# ETHERNET.net
KiCad netlist of a schematic drawn in Altium Designer
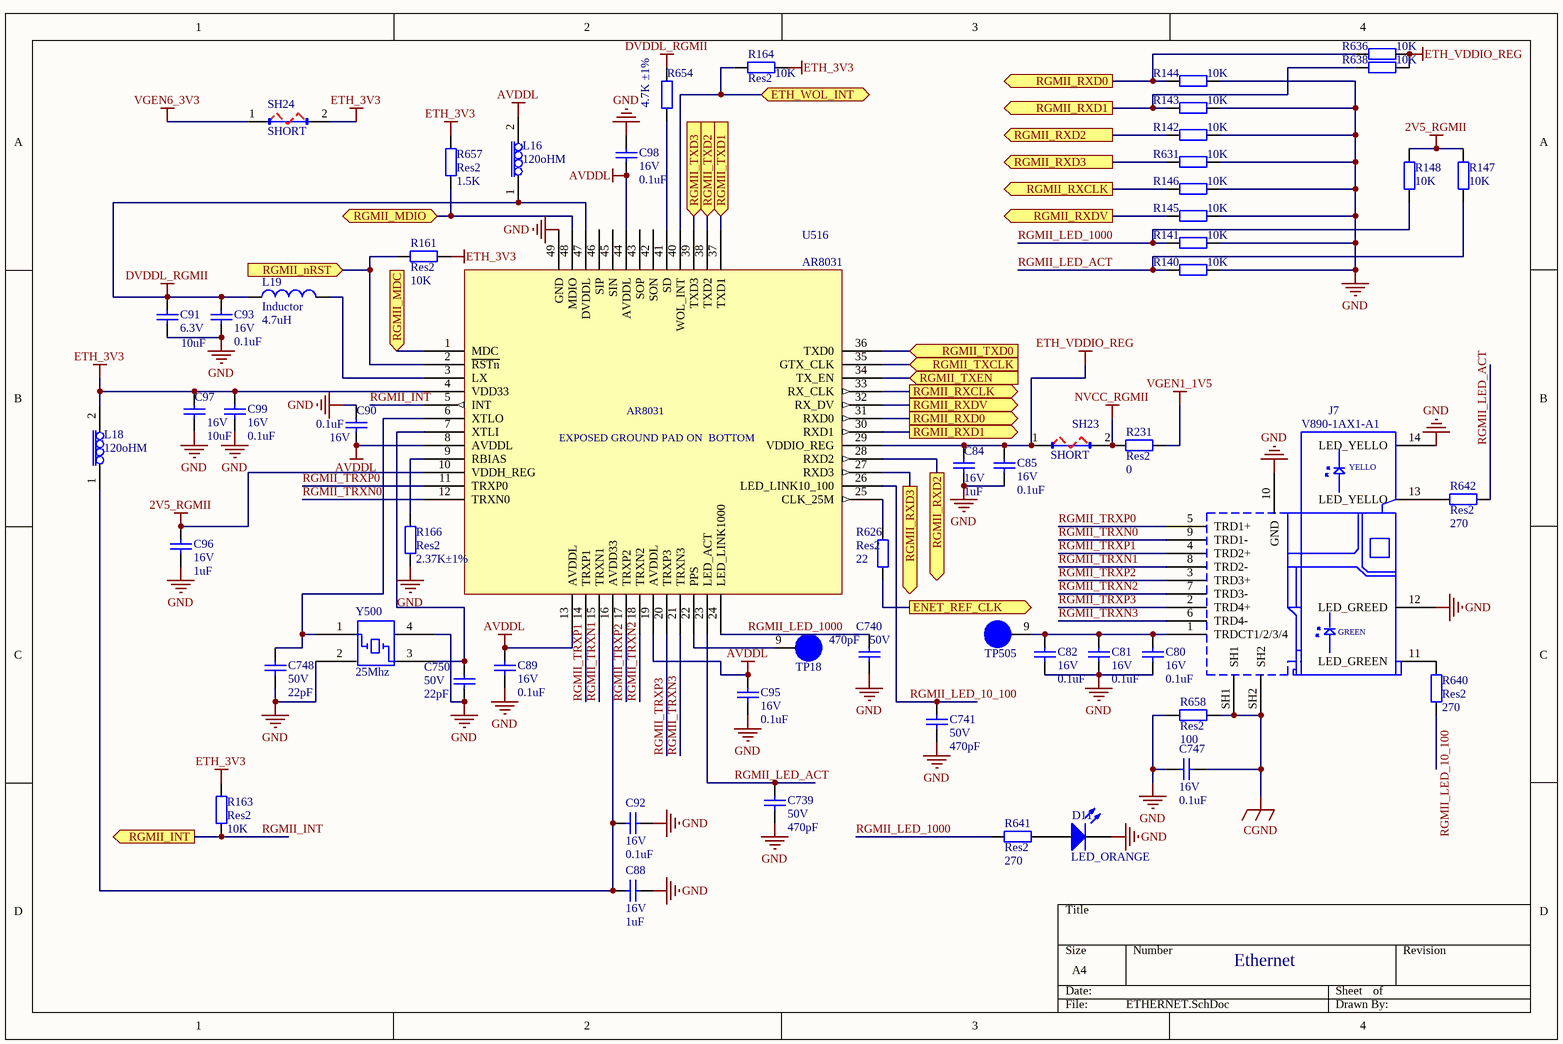
[diagram p0: ETHERNET.SchDoc]

(export (version "E")
  (design (tool "Eeschema 10.0.6"))
  (components
    (comp (ref "C80")
      (value "16V")
      (footprint "0402")
      (description "Capacitor")
      (fields (field (name "ALTIUM_VALUE") "0.1uF") (field (name "PUBLISHER") "Altium Limited"))
      (libsource (lib "Miscellaneous Devices") (part "Cap"))
    )
    (comp (ref "C81")
      (value "16V")
      (footprint "0402")
      (description "Capacitor")
      (fields (field (name "ALTIUM_VALUE") "0.1uF") (field (name "PUBLISHER") "Altium Limited"))
      (libsource (lib "Miscellaneous Devices") (part "Cap"))
    )
    (comp (ref "C82")
      (value "16V")
      (footprint "0402")
      (description "Capacitor")
      (fields (field (name "ALTIUM_VALUE") "0.1uF") (field (name "PUBLISHER") "Altium Limited"))
      (libsource (lib "Miscellaneous Devices") (part "Cap"))
    )
    (comp (ref "C84")
      (value "16V")
      (footprint "0603")
      (description "Capacitor")
      (fields (field (name "ALTIUM_VALUE") "1uF") (field (name "PUBLISHER") "Altium Limited"))
      (libsource (lib "Miscellaneous Devices") (part "Cap"))
    )
    (comp (ref "C85")
      (value "16V")
      (footprint "0402")
      (description "Capacitor")
      (fields (field (name "ALTIUM_VALUE") "0.1uF") (field (name "PUBLISHER") "Altium Limited"))
      (libsource (lib "Miscellaneous Devices") (part "Cap"))
    )
    (comp (ref "C88")
      (value "16V")
      (footprint "0603")
      (description "Capacitor")
      (fields (field (name "ALTIUM_VALUE") "1uF") (field (name "PUBLISHER") "Altium Limited"))
      (libsource (lib "Miscellaneous Devices") (part "Cap"))
    )
    (comp (ref "C89")
      (value "16V")
      (footprint "0402")
      (description "Capacitor")
      (fields (field (name "ALTIUM_VALUE") "0.1uF") (field (name "PUBLISHER") "Altium Limited"))
      (libsource (lib "Miscellaneous Devices") (part "Cap"))
    )
    (comp (ref "C90")
      (value "16V")
      (footprint "0402")
      (description "Capacitor")
      (fields (field (name "ALTIUM_VALUE") "0.1uF") (field (name "PUBLISHER") "Altium Limited"))
      (libsource (lib "Miscellaneous Devices") (part "Cap"))
    )
    (comp (ref "C91")
      (value "6.3V")
      (footprint "0603")
      (description "Capacitor")
      (fields (field (name "ALTIUM_VALUE") "10uF") (field (name "PUBLISHER") "Altium Limited"))
      (libsource (lib "Miscellaneous Devices") (part "Cap"))
    )
    (comp (ref "C92")
      (value "16V")
      (footprint "0402")
      (description "Capacitor")
      (fields (field (name "ALTIUM_VALUE") "0.1uF") (field (name "PUBLISHER") "Altium Limited"))
      (libsource (lib "Miscellaneous Devices") (part "Cap"))
    )
    (comp (ref "C93")
      (value "16V")
      (footprint "0402")
      (description "Capacitor")
      (fields (field (name "ALTIUM_VALUE") "0.1uF") (field (name "PUBLISHER") "Altium Limited"))
      (libsource (lib "Miscellaneous Devices") (part "Cap"))
    )
    (comp (ref "C95")
      (value "16V")
      (footprint "0402")
      (description "Capacitor")
      (fields (field (name "ALTIUM_VALUE") "0.1uF") (field (name "PUBLISHER") "Altium Limited"))
      (libsource (lib "Miscellaneous Devices") (part "Cap"))
    )
    (comp (ref "C96")
      (value "16V")
      (footprint "0603")
      (description "Capacitor")
      (fields (field (name "ALTIUM_VALUE") "1uF") (field (name "PUBLISHER") "Altium Limited"))
      (libsource (lib "Miscellaneous Devices") (part "Cap"))
    )
    (comp (ref "C97")
      (value "16V")
      (footprint "0603")
      (description "Capacitor")
      (fields (field (name "ALTIUM_VALUE") "10uF") (field (name "PUBLISHER") "Altium Limited"))
      (libsource (lib "Miscellaneous Devices") (part "Cap"))
    )
    (comp (ref "C98")
      (value "16V")
      (footprint "0402")
      (description "Capacitor")
      (fields (field (name "ALTIUM_VALUE") "0.1uF") (field (name "PUBLISHER") "Altium Limited"))
      (libsource (lib "Miscellaneous Devices") (part "Cap"))
    )
    (comp (ref "C99")
      (value "16V")
      (footprint "0402")
      (description "Capacitor")
      (fields (field (name "ALTIUM_VALUE") "0.1uF") (field (name "PUBLISHER") "Altium Limited"))
      (libsource (lib "Miscellaneous Devices") (part "Cap"))
    )
    (comp (ref "C739")
      (value "50V")
      (footprint "0402")
      (description "Capacitor")
      (fields (field (name "ALTIUM_VALUE") "470pF") (field (name "PUBLISHER") "Altium Limited"))
      (libsource (lib "Miscellaneous Devices") (part "Cap"))
    )
    (comp (ref "C740")
      (value "50V")
      (footprint "0402")
      (description "Capacitor")
      (fields (field (name "ALTIUM_VALUE") "470pF") (field (name "PUBLISHER") "Altium Limited"))
      (libsource (lib "Miscellaneous Devices") (part "Cap"))
    )
    (comp (ref "C741")
      (value "50V")
      (footprint "0402")
      (description "Capacitor")
      (fields (field (name "ALTIUM_VALUE") "470pF") (field (name "PUBLISHER") "Altium Limited"))
      (libsource (lib "Miscellaneous Devices") (part "Cap"))
    )
    (comp (ref "C747")
      (value "16V")
      (footprint "0402")
      (description "Capacitor")
      (fields (field (name "ALTIUM_VALUE") "0.1uF") (field (name "PUBLISHER") "Altium Limited"))
      (libsource (lib "Miscellaneous Devices") (part "Cap"))
    )
    (comp (ref "C748")
      (value "50V")
      (footprint "0402")
      (description "Capacitor")
      (fields (field (name "ALTIUM_VALUE") "22pF") (field (name "PUBLISHER") "Altium Limited"))
      (libsource (lib "Miscellaneous Devices") (part "Cap"))
    )
    (comp (ref "C750")
      (value "50V")
      (footprint "0402")
      (description "Capacitor")
      (fields (field (name "ALTIUM_VALUE") "22pF") (field (name "PUBLISHER") "Altium Limited"))
      (libsource (lib "Miscellaneous Devices") (part "Cap"))
    )
    (comp (ref "D11")
      (value "LED_ORANGE")
      (footprint "LED_0603")
      (description "Typical INFRARED GaAs LED")
      (fields (field (name "PUBLISHER") "Altium Limited"))
      (libsource (lib "Miscellaneous Devices") (part "LED0"))
    )
    (comp (ref "J7")
      (value "V890-1AX1-A1")
      (footprint "V890-1AX1-A1")
      (libsource (lib "IMX6DL") (part "Ethernet PORT"))
    )
    (comp (ref "L16") (value "120oHM") (footprint "0603") (libsource (lib "IMX6DL") (part "magnetic BEAD")))
    (comp (ref "L18") (value "120oHM") (footprint "0603") (libsource (lib "IMX6DL") (part "magnetic BEAD")))
    (comp (ref "L19")
      (value "Inductor")
      (footprint "VLS3012-4R7M1R0")
      (fields (field (name "ALTIUM_VALUE") "4.7uH") (field (name "PUBLISHER") "Altium Limited"))
      (libsource (lib "Miscellaneous Devices") (part "Inductor"))
    )
    (comp (ref "R140")
      (value "10K")
      (footprint "0402")
      (description "Resistor")
      (fields (field (name "Comment") "Res2") (field (name "PUBLISHER") "Altium Limited"))
      (libsource (lib "Miscellaneous Devices") (part "Res2"))
    )
    (comp (ref "R141")
      (value "10K")
      (footprint "0402")
      (description "Resistor")
      (fields (field (name "Comment") "Res2") (field (name "PUBLISHER") "Altium Limited"))
      (libsource (lib "Miscellaneous Devices") (part "Res2"))
    )
    (comp (ref "R142")
      (value "10K")
      (footprint "0402")
      (description "Resistor")
      (fields (field (name "Comment") "Res2") (field (name "PUBLISHER") "Altium Limited"))
      (libsource (lib "Miscellaneous Devices") (part "Res2"))
    )
    (comp (ref "R143")
      (value "10K")
      (footprint "0402")
      (description "Resistor")
      (fields (field (name "Comment") "Res2") (field (name "PUBLISHER") "Altium Limited"))
      (libsource (lib "Miscellaneous Devices") (part "Res2"))
    )
    (comp (ref "R144")
      (value "10K")
      (footprint "0402")
      (description "Resistor")
      (fields (field (name "Comment") "Res2") (field (name "PUBLISHER") "Altium Limited"))
      (libsource (lib "Miscellaneous Devices") (part "Res2"))
    )
    (comp (ref "R145")
      (value "10K")
      (footprint "0402")
      (description "Resistor")
      (fields (field (name "Comment") "Res2") (field (name "PUBLISHER") "Altium Limited"))
      (libsource (lib "Miscellaneous Devices") (part "Res2"))
    )
    (comp (ref "R146")
      (value "10K")
      (footprint "0402")
      (description "Resistor")
      (fields (field (name "Comment") "Res2") (field (name "PUBLISHER") "Altium Limited"))
      (libsource (lib "Miscellaneous Devices") (part "Res2"))
    )
    (comp (ref "R147")
      (value "10K")
      (footprint "0402")
      (description "Resistor")
      (fields (field (name "Comment") "Res2") (field (name "PUBLISHER") "Altium Limited"))
      (libsource (lib "") (part "Res2_2"))
    )
    (comp (ref "R148")
      (value "10K")
      (footprint "0402")
      (description "Resistor")
      (fields (field (name "Comment") "Res2") (field (name "PUBLISHER") "Altium Limited"))
      (libsource (lib "") (part "Res2_2"))
    )
    (comp (ref "R161")
      (value "Res2")
      (footprint "0402")
      (description "Resistor")
      (fields (field (name "ALTIUM_VALUE") "10K") (field (name "PUBLISHER") "Altium Limited"))
      (libsource (lib "Miscellaneous Devices") (part "Res2"))
    )
    (comp (ref "R163")
      (value "Res2")
      (footprint "0402")
      (description "Resistor")
      (fields (field (name "ALTIUM_VALUE") "10K") (field (name "PUBLISHER") "Altium Limited"))
      (libsource (lib "") (part "Res2_2"))
    )
    (comp (ref "R164")
      (value "Res2")
      (footprint "0402")
      (description "Resistor")
      (fields (field (name "ALTIUM_VALUE") "10K") (field (name "PUBLISHER") "Altium Limited"))
      (libsource (lib "") (part "Res2_1"))
    )
    (comp (ref "R166")
      (value "Res2")
      (footprint "0402")
      (description "Resistor")
      (fields (field (name "ALTIUM_VALUE") "2.37K±1%") (field (name "PUBLISHER") "Altium Limited"))
      (libsource (lib "") (part "Res2_2"))
    )
    (comp (ref "R231")
      (value "Res2")
      (footprint "0603")
      (description "Resistor")
      (fields (field (name "ALTIUM_VALUE") "0") (field (name "PUBLISHER") "Altium Limited"))
      (libsource (lib "") (part "Res2_1"))
    )
    (comp (ref "R626")
      (value "Res2")
      (footprint "0603")
      (description "Resistor")
      (fields (field (name "ALTIUM_VALUE") "22") (field (name "PUBLISHER") "Altium Limited"))
      (libsource (lib "") (part "Res2_3"))
    )
    (comp (ref "R631")
      (value "10K")
      (footprint "0402")
      (description "Resistor")
      (fields (field (name "Comment") "Res2") (field (name "PUBLISHER") "Altium Limited"))
      (libsource (lib "Miscellaneous Devices") (part "Res2"))
    )
    (comp (ref "R636")
      (value "10K")
      (footprint "0402")
      (description "Resistor")
      (fields (field (name "Comment") "Res2") (field (name "PUBLISHER") "Altium Limited"))
      (libsource (lib "") (part "Res2_1"))
    )
    (comp (ref "R638")
      (value "10K")
      (footprint "0402")
      (description "Resistor")
      (fields (field (name "Comment") "Res2") (field (name "PUBLISHER") "Altium Limited"))
      (libsource (lib "") (part "Res2_1"))
    )
    (comp (ref "R640")
      (value "Res2")
      (footprint "0402")
      (description "Resistor")
      (fields (field (name "ALTIUM_VALUE") "270") (field (name "PUBLISHER") "Altium Limited"))
      (libsource (lib "") (part "Res2_2"))
    )
    (comp (ref "R641")
      (value "Res2")
      (footprint "0402")
      (description "Resistor")
      (fields (field (name "ALTIUM_VALUE") "270") (field (name "PUBLISHER") "Altium Limited"))
      (libsource (lib "") (part "Res2_1"))
    )
    (comp (ref "R642")
      (value "Res2")
      (footprint "0402")
      (description "Resistor")
      (fields (field (name "ALTIUM_VALUE") "270") (field (name "PUBLISHER") "Altium Limited"))
      (libsource (lib "") (part "Res2_1"))
    )
    (comp (ref "R654")
      (value "±1%")
      (footprint "0402")
      (description "Resistor")
      (fields (field (name "ALTIUM_VALUE") "4.7K") (field (name "PUBLISHER") "Altium Limited"))
      (libsource (lib "") (part "Res2_2"))
    )
    (comp (ref "R657")
      (value "Res2")
      (footprint "0402")
      (description "Resistor")
      (fields (field (name "ALTIUM_VALUE") "1.5K") (field (name "PUBLISHER") "Altium Limited"))
      (libsource (lib "") (part "Res2_2"))
    )
    (comp (ref "R658")
      (value "Res2")
      (footprint "0402")
      (description "Resistor")
      (fields (field (name "ALTIUM_VALUE") "100") (field (name "PUBLISHER") "Altium Limited"))
      (libsource (lib "") (part "Res2_1"))
    )
    (comp (ref "SH23")
      (value "SHORT")
      (footprint "SHORT_SH")
      (libsource (lib "IMX6DL") (part "SOLDER SHORT"))
    )
    (comp (ref "SH24")
      (value "SHORT")
      (footprint "SHORT_SH")
      (libsource (lib "IMX6DL") (part "SOLDER SHORT"))
    )
    (comp (ref "TP18") (value "TP test") (libsource (lib "IMX6DL") (part "TP test")))
    (comp (ref "TP505") (value "TP test") (libsource (lib "IMX6DL") (part "TP test")))
    (comp (ref "U516") (value "AR8031") (footprint "AR8031") (libsource (lib "IMX6DL") (part "AR8031")))
    (comp (ref "Y500") (value "25Mhz") (footprint "XTAL-ABMM-25M") (libsource (lib "IMX6DL") (part "XTAL")))
  )
  (nets
    (net (code "1") (name "/ENET_REF_CLK") (class "Default")
      (node (ref "R626") (pin "2") (pinfunction "2_2") (pintype "passive"))
    )
    (net (code "2") (name "/ETH_WOL_INT") (class "Default")
      (node (ref "R164") (pin "2") (pinfunction "2_2") (pintype "passive"))
      (node (ref "U516") (pin "40") (pinfunction "WOL_INT_40") (pintype "passive"))
    )
    (net (code "3") (name "/RGMII_INT") (class "Default")
      (node (ref "R163") (pin "1") (pinfunction "1_1") (pintype "passive"))
      (node (ref "U516") (pin "5") (pinfunction "INT_5") (pintype "output"))
    )
    (net (code "4") (name "/RGMII_LED_10_100") (class "Default")
      (node (ref "C741") (pin "2") (pinfunction "2_2") (pintype "passive"))
      (node (ref "R640") (pin "1") (pinfunction "1_1") (pintype "passive"))
      (node (ref "U516") (pin "26") (pinfunction "LED_LINK10_100_26") (pintype "passive"))
    )
    (net (code "5") (name "/RGMII_LED_1000") (class "Default")
      (node (ref "C740") (pin "1") (pinfunction "1_1") (pintype "passive"))
      (node (ref "R141") (pin "1") (pinfunction "1_1") (pintype "passive"))
      (node (ref "R148") (pin "1") (pinfunction "1_1") (pintype "passive"))
      (node (ref "R641") (pin "2") (pinfunction "2_2") (pintype "passive"))
      (node (ref "U516") (pin "24") (pinfunction "LED_LINK1000_24") (pintype "passive"))
    )
    (net (code "6") (name "/RGMII_LED_ACT") (class "Default")
      (node (ref "C739") (pin "2") (pinfunction "2_2") (pintype "passive"))
      (node (ref "R140") (pin "1") (pinfunction "1_1") (pintype "passive"))
      (node (ref "R147") (pin "1") (pinfunction "1_1") (pintype "passive"))
      (node (ref "R642") (pin "1") (pinfunction "1_1") (pintype "passive"))
      (node (ref "U516") (pin "23") (pinfunction "LED_ACT_23") (pintype "passive"))
    )
    (net (code "7") (name "/RGMII_MDC") (class "Default")
      (node (ref "U516") (pin "1") (pinfunction "MDC_1") (pintype "passive"))
    )
    (net (code "8") (name "/RGMII_MDIO") (class "Default")
      (node (ref "R657") (pin "1") (pinfunction "1_1") (pintype "passive"))
      (node (ref "U516") (pin "48") (pinfunction "MDIO_48") (pintype "passive"))
    )
    (net (code "9") (name "/RGMII_RXCLK") (class "Default")
      (node (ref "R146") (pin "1") (pinfunction "1_1") (pintype "passive"))
      (node (ref "U516") (pin "33") (pinfunction "RX_CLK_33") (pintype "output"))
    )
    (net (code "10") (name "/RGMII_RXD0") (class "Default")
      (node (ref "R144") (pin "1") (pinfunction "1_1") (pintype "passive"))
      (node (ref "R636") (pin "2") (pinfunction "2_2") (pintype "passive"))
      (node (ref "U516") (pin "31") (pinfunction "RXD0_31") (pintype "output"))
    )
    (net (code "11") (name "/RGMII_RXD1") (class "Default")
      (node (ref "R143") (pin "1") (pinfunction "1_1") (pintype "passive"))
      (node (ref "R638") (pin "2") (pinfunction "2_2") (pintype "passive"))
      (node (ref "U516") (pin "30") (pinfunction "RXD1_30") (pintype "output"))
    )
    (net (code "12") (name "/RGMII_RXD2") (class "Default")
      (node (ref "R142") (pin "1") (pinfunction "1_1") (pintype "passive"))
      (node (ref "U516") (pin "28") (pinfunction "RXD2_28") (pintype "output"))
    )
    (net (code "13") (name "/RGMII_RXD3") (class "Default")
      (node (ref "R631") (pin "1") (pinfunction "1_1") (pintype "passive"))
      (node (ref "U516") (pin "27") (pinfunction "RXD3_27") (pintype "output"))
    )
    (net (code "14") (name "/RGMII_RXDV") (class "Default")
      (node (ref "R145") (pin "1") (pinfunction "1_1") (pintype "passive"))
      (node (ref "U516") (pin "32") (pinfunction "RX_DV_32") (pintype "output"))
    )
    (net (code "15") (name "/RGMII_TRXN0") (class "Default")
      (node (ref "J7") (pin "9") (pinfunction "TRD1-_9") (pintype "passive"))
      (node (ref "U516") (pin "12") (pinfunction "TRXN0_12") (pintype "passive"))
    )
    (net (code "16") (name "/RGMII_TRXN1") (class "Default")
      (node (ref "J7") (pin "8") (pinfunction "TRD2-_8") (pintype "passive"))
      (node (ref "U516") (pin "15") (pinfunction "TRXN1_15") (pintype "passive"))
    )
    (net (code "17") (name "/RGMII_TRXN2") (class "Default")
      (node (ref "J7") (pin "7") (pinfunction "TRD3-_7") (pintype "passive"))
      (node (ref "U516") (pin "18") (pinfunction "TRXN2_18") (pintype "passive"))
    )
    (net (code "18") (name "/RGMII_TRXN3") (class "Default")
      (node (ref "J7") (pin "6") (pinfunction "TRD4-_6") (pintype "passive"))
      (node (ref "U516") (pin "21") (pinfunction "TRXN3_21") (pintype "passive"))
    )
    (net (code "19") (name "/RGMII_TRXP0") (class "Default")
      (node (ref "J7") (pin "5") (pinfunction "TRD1+_5") (pintype "passive"))
      (node (ref "U516") (pin "11") (pinfunction "TRXP0_11") (pintype "passive"))
    )
    (net (code "20") (name "/RGMII_TRXP1") (class "Default")
      (node (ref "J7") (pin "4") (pinfunction "TRD2+_4") (pintype "passive"))
      (node (ref "U516") (pin "14") (pinfunction "TRXP1_14") (pintype "passive"))
    )
    (net (code "21") (name "/RGMII_TRXP2") (class "Default")
      (node (ref "J7") (pin "3") (pinfunction "TRD3+_3") (pintype "passive"))
      (node (ref "U516") (pin "17") (pinfunction "TRXP2_17") (pintype "passive"))
    )
    (net (code "22") (name "/RGMII_TRXP3") (class "Default")
      (node (ref "J7") (pin "2") (pinfunction "TRD4+_2") (pintype "passive"))
      (node (ref "U516") (pin "20") (pinfunction "TRXP3_20") (pintype "passive"))
    )
    (net (code "23") (name "/RGMII_TXCLK") (class "Default")
      (node (ref "U516") (pin "35") (pinfunction "GTX_CLK_35") (pintype "passive"))
    )
    (net (code "24") (name "/RGMII_TXD0") (class "Default")
      (node (ref "U516") (pin "36") (pinfunction "TXD0_36") (pintype "passive"))
    )
    (net (code "25") (name "/RGMII_TXD1") (class "Default")
      (node (ref "U516") (pin "37") (pinfunction "TXD1_37") (pintype "passive"))
    )
    (net (code "26") (name "/RGMII_TXD2") (class "Default")
      (node (ref "U516") (pin "38") (pinfunction "TXD2_38") (pintype "passive"))
    )
    (net (code "27") (name "/RGMII_TXD3") (class "Default")
      (node (ref "U516") (pin "39") (pinfunction "TXD3_39") (pintype "passive"))
    )
    (net (code "28") (name "/RGMII_TXEN") (class "Default")
      (node (ref "U516") (pin "34") (pinfunction "TX_EN_34") (pintype "passive"))
    )
    (net (code "29") (name "/RGMII_nRST") (class "Default")
      (node (ref "R161") (pin "1") (pinfunction "1_1") (pintype "passive"))
      (node (ref "U516") (pin "2") (pinfunction "~{RSTn}_2") (pintype "passive"))
    )
    (net (code "30") (name "2V5_RGMII") (class "Default")
      (node (ref "C96") (pin "2") (pinfunction "2_2") (pintype "passive"))
      (node (ref "R147") (pin "2") (pinfunction "2_2") (pintype "passive"))
      (node (ref "R148") (pin "2") (pinfunction "2_2") (pintype "passive"))
      (node (ref "U516") (pin "10") (pinfunction "VDDH_REG_10") (pintype "passive"))
    )
    (net (code "31") (name "AVDDL") (class "Default")
      (node (ref "C89") (pin "2") (pinfunction "2_2") (pintype "passive"))
      (node (ref "C90") (pin "1") (pinfunction "1_1") (pintype "passive"))
      (node (ref "C95") (pin "2") (pinfunction "2_2") (pintype "passive"))
      (node (ref "C98") (pin "2") (pinfunction "2_2") (pintype "passive"))
      (node (ref "L16") (pin "2") (pinfunction "VSS4_2") (pintype "passive"))
      (node (ref "U516") (pin "13") (pinfunction "AVDDL_13") (pintype "passive"))
      (node (ref "U516") (pin "19") (pinfunction "AVDDL_19") (pintype "passive"))
      (node (ref "U516") (pin "44") (pinfunction "AVDDL_44") (pintype "passive"))
      (node (ref "U516") (pin "8") (pinfunction "AVDDL_8") (pintype "passive"))
    )
    (net (code "32") (name "CGND") (class "Default")
      (node (ref "C747") (pin "1") (pinfunction "1_1") (pintype "passive"))
      (node (ref "J7") (pin "SH1") (pinfunction "SH1_SH1") (pintype "passive"))
      (node (ref "J7") (pin "SH2") (pinfunction "SH2_SH2") (pintype "passive"))
      (node (ref "R658") (pin "1") (pinfunction "1_1") (pintype "passive"))
    )
    (net (code "33") (name "DVDDL_RGMII") (class "Default")
      (node (ref "C91") (pin "2") (pinfunction "2_2") (pintype "passive"))
      (node (ref "C93") (pin "2") (pinfunction "2_2") (pintype "passive"))
      (node (ref "L16") (pin "1") (pinfunction "VSS3_1") (pintype "passive"))
      (node (ref "L19") (pin "1") (pinfunction "1_1") (pintype "passive"))
      (node (ref "R654") (pin "2") (pinfunction "2_2") (pintype "passive"))
      (node (ref "U516") (pin "47") (pinfunction "DVDDL_47") (pintype "passive"))
    )
    (net (code "34") (name "ETH_3V3") (class "Default")
      (node (ref "C97") (pin "2") (pinfunction "2_2") (pintype "passive"))
      (node (ref "C99") (pin "2") (pinfunction "2_2") (pintype "passive"))
      (node (ref "L18") (pin "2") (pinfunction "VSS4_2") (pintype "passive"))
      (node (ref "R161") (pin "2") (pinfunction "2_2") (pintype "passive"))
      (node (ref "R163") (pin "2") (pinfunction "2_2") (pintype "passive"))
      (node (ref "R164") (pin "1") (pinfunction "1_1") (pintype "passive"))
      (node (ref "R657") (pin "2") (pinfunction "2_2") (pintype "passive"))
      (node (ref "SH24") (pin "2") (pinfunction "VCCIO_2") (pintype "passive"))
      (node (ref "U516") (pin "4") (pinfunction "VDD33_4") (pintype "passive"))
    )
    (net (code "35") (name "ETH_VDDIO_REG") (class "Default")
      (node (ref "C84") (pin "2") (pinfunction "2_2") (pintype "passive"))
      (node (ref "C85") (pin "2") (pinfunction "2_2") (pintype "passive"))
      (node (ref "R636") (pin "1") (pinfunction "1_1") (pintype "passive"))
      (node (ref "R638") (pin "1") (pinfunction "1_1") (pintype "passive"))
      (node (ref "SH23") (pin "1") (pinfunction "VCCIO_1") (pintype "passive"))
      (node (ref "U516") (pin "29") (pinfunction "VDDIO_REG_29") (pintype "passive"))
    )
    (net (code "36") (name "GND") (class "Default")
      (node (ref "C739") (pin "1") (pinfunction "1_1") (pintype "passive"))
      (node (ref "C740") (pin "2") (pinfunction "2_2") (pintype "passive"))
      (node (ref "C741") (pin "1") (pinfunction "1_1") (pintype "passive"))
      (node (ref "C747") (pin "2") (pinfunction "2_2") (pintype "passive"))
      (node (ref "C748") (pin "1") (pinfunction "1_1") (pintype "passive"))
      (node (ref "C750") (pin "1") (pinfunction "1_1") (pintype "passive"))
      (node (ref "C80") (pin "1") (pinfunction "1_1") (pintype "passive"))
      (node (ref "C81") (pin "1") (pinfunction "1_1") (pintype "passive"))
      (node (ref "C82") (pin "1") (pinfunction "1_1") (pintype "passive"))
      (node (ref "C84") (pin "1") (pinfunction "1_1") (pintype "passive"))
      (node (ref "C85") (pin "1") (pinfunction "1_1") (pintype "passive"))
      (node (ref "C88") (pin "1") (pinfunction "1_1") (pintype "passive"))
      (node (ref "C89") (pin "1") (pinfunction "1_1") (pintype "passive"))
      (node (ref "C90") (pin "2") (pinfunction "2_2") (pintype "passive"))
      (node (ref "C91") (pin "1") (pinfunction "1_1") (pintype "passive"))
      (node (ref "C92") (pin "1") (pinfunction "1_1") (pintype "passive"))
      (node (ref "C93") (pin "1") (pinfunction "1_1") (pintype "passive"))
      (node (ref "C95") (pin "1") (pinfunction "1_1") (pintype "passive"))
      (node (ref "C96") (pin "1") (pinfunction "1_1") (pintype "passive"))
      (node (ref "C97") (pin "1") (pinfunction "1_1") (pintype "passive"))
      (node (ref "C98") (pin "1") (pinfunction "1_1") (pintype "passive"))
      (node (ref "C99") (pin "1") (pinfunction "1_1") (pintype "passive"))
      (node (ref "D11") (pin "2") (pinfunction "K_2") (pintype "passive"))
      (node (ref "J7") (pin "10") (pinfunction "GND_10") (pintype "passive"))
      (node (ref "J7") (pin "12") (pinfunction "LED_GREED_12") (pintype "passive"))
      (node (ref "J7") (pin "14") (pinfunction "LED_YELLO_14") (pintype "passive"))
      (node (ref "R140") (pin "2") (pinfunction "2_2") (pintype "passive"))
      (node (ref "R141") (pin "2") (pinfunction "2_2") (pintype "passive"))
      (node (ref "R142") (pin "2") (pinfunction "2_2") (pintype "passive"))
      (node (ref "R143") (pin "2") (pinfunction "2_2") (pintype "passive"))
      (node (ref "R144") (pin "2") (pinfunction "2_2") (pintype "passive"))
      (node (ref "R145") (pin "2") (pinfunction "2_2") (pintype "passive"))
      (node (ref "R146") (pin "2") (pinfunction "2_2") (pintype "passive"))
      (node (ref "R166") (pin "1") (pinfunction "1_1") (pintype "passive"))
      (node (ref "R631") (pin "2") (pinfunction "2_2") (pintype "passive"))
      (node (ref "R658") (pin "2") (pinfunction "2_2") (pintype "passive"))
      (node (ref "U516") (pin "49") (pinfunction "GND_49") (pintype "passive"))
      (node (ref "Y500") (pin "2") (pinfunction "58_2") (pintype "passive"))
      (node (ref "Y500") (pin "4") (pinfunction "60_4") (pintype "passive"))
    )
    (net (code "37") (name "NVCC_RGMII") (class "Default")
      (node (ref "R231") (pin "2") (pinfunction "2_2") (pintype "passive"))
      (node (ref "SH23") (pin "2") (pinfunction "VCCIO_2") (pintype "passive"))
    )
    (net (code "38") (name "Net-(D11-A)") (class "Default")
      (node (ref "D11") (pin "1") (pinfunction "A_1") (pintype "passive"))
      (node (ref "R641") (pin "1") (pinfunction "1_1") (pintype "passive"))
    )
    (net (code "39") (name "Net-(J7-LED_GREEN)") (class "Default")
      (node (ref "J7") (pin "11") (pinfunction "LED_GREEN_11") (pintype "passive"))
      (node (ref "R640") (pin "2") (pinfunction "2_2") (pintype "passive"))
    )
    (net (code "40") (name "Net-(J7-LED_YELLO-Pad13)") (class "Default")
      (node (ref "J7") (pin "13") (pinfunction "LED_YELLO_13") (pintype "passive"))
      (node (ref "R642") (pin "2") (pinfunction "2_2") (pintype "passive"))
    )
    (net (code "41") (name "Net-(J7-TRDCT1{slash}2{slash}3{slash}4)") (class "Default")
      (node (ref "C80") (pin "2") (pinfunction "2_2") (pintype "passive"))
      (node (ref "C81") (pin "2") (pinfunction "2_2") (pintype "passive"))
      (node (ref "C82") (pin "2") (pinfunction "2_2") (pintype "passive"))
      (node (ref "J7") (pin "1") (pinfunction "TRDCT1/2/3/4_1") (pintype "passive"))
      (node (ref "TP505") (pin "9") (pinfunction "S_9") (pintype "passive"))
    )
    (net (code "42") (name "Net-(L18-VSS3)") (class "Default")
      (node (ref "C88") (pin "2") (pinfunction "2_2") (pintype "passive"))
      (node (ref "C92") (pin "2") (pinfunction "2_2") (pintype "passive"))
      (node (ref "L18") (pin "1") (pinfunction "VSS3_1") (pintype "passive"))
      (node (ref "U516") (pin "16") (pinfunction "AVDD33_16") (pintype "passive"))
    )
    (net (code "43") (name "Net-(TP18-S)") (class "Default")
      (node (ref "TP18") (pin "9") (pinfunction "S_9") (pintype "passive"))
      (node (ref "U516") (pin "22") (pinfunction "PPS_22") (pintype "passive"))
    )
    (net (code "44") (name "Net-(U516-CLK_25M)") (class "Default")
      (node (ref "R626") (pin "1") (pinfunction "1_1") (pintype "passive"))
      (node (ref "U516") (pin "25") (pinfunction "CLK_25M_25") (pintype "output"))
    )
    (net (code "45") (name "Net-(U516-LX)") (class "Default")
      (node (ref "L19") (pin "2") (pinfunction "2_2") (pintype "passive"))
      (node (ref "U516") (pin "3") (pinfunction "LX_3") (pintype "passive"))
    )
    (net (code "46") (name "Net-(U516-RBIAS)") (class "Default")
      (node (ref "R166") (pin "2") (pinfunction "2_2") (pintype "passive"))
      (node (ref "U516") (pin "9") (pinfunction "RBIAS_9") (pintype "passive"))
    )
    (net (code "47") (name "Net-(U516-SD)") (class "Default")
      (node (ref "R654") (pin "1") (pinfunction "1_1") (pintype "passive"))
      (node (ref "U516") (pin "41") (pinfunction "SD_41") (pintype "passive"))
    )
    (net (code "48") (name "Net-(U516-XTLI)") (class "Default")
      (node (ref "C750") (pin "2") (pinfunction "2_2") (pintype "passive"))
      (node (ref "U516") (pin "7") (pinfunction "XTLI_7") (pintype "passive"))
      (node (ref "Y500") (pin "3") (pinfunction "59_3") (pintype "passive"))
    )
    (net (code "49") (name "Net-(U516-XTLO)") (class "Default")
      (node (ref "C748") (pin "2") (pinfunction "2_2") (pintype "passive"))
      (node (ref "U516") (pin "6") (pinfunction "XTLO_6") (pintype "passive"))
      (node (ref "Y500") (pin "1") (pinfunction "57_1") (pintype "passive"))
    )
    (net (code "50") (name "VGEN1_1V5") (class "Default")
      (node (ref "R231") (pin "1") (pinfunction "1_1") (pintype "passive"))
    )
    (net (code "51") (name "VGEN6_3V3") (class "Default")
      (node (ref "SH24") (pin "1") (pinfunction "VCCIO_1") (pintype "passive"))
    )
    (net (code "52") (name "unconnected-(U516-SIN-Pad45)") (class "Default")
      (node (ref "U516") (pin "45") (pinfunction "SIN_45") (pintype "passive"))
    )
    (net (code "53") (name "unconnected-(U516-SIP-Pad46)") (class "Default")
      (node (ref "U516") (pin "46") (pinfunction "SIP_46") (pintype "passive"))
    )
    (net (code "54") (name "unconnected-(U516-SON-Pad42)") (class "Default")
      (node (ref "U516") (pin "42") (pinfunction "SON_42") (pintype "passive"))
    )
    (net (code "55") (name "unconnected-(U516-SOP-Pad43)") (class "Default")
      (node (ref "U516") (pin "43") (pinfunction "SOP_43") (pintype "passive"))
    )
  )
)
